# C-07_CPU_MISC.net
KiCad netlist of a schematic drawn in Altium Designer
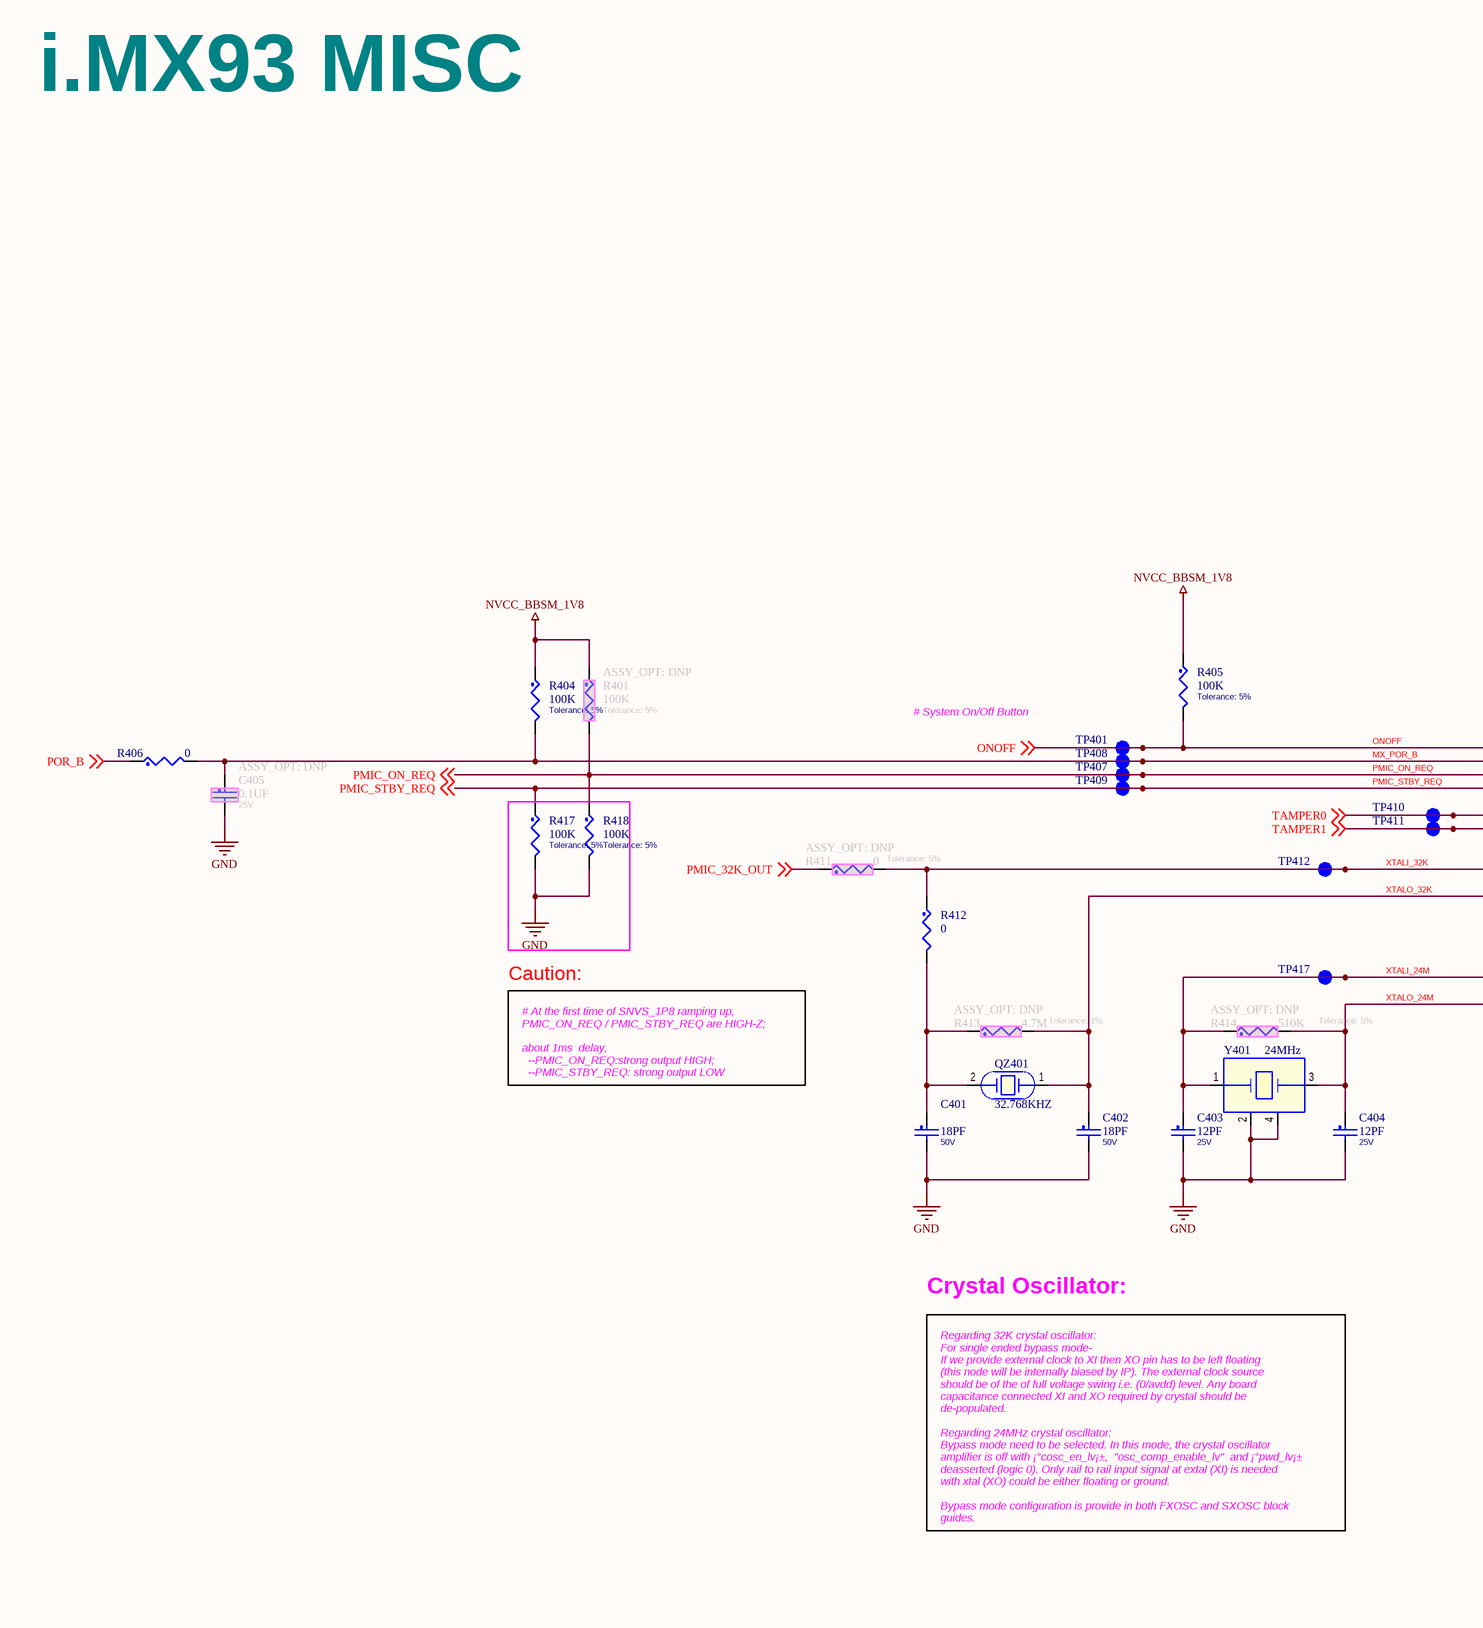
[diagram p0: C-07 CPU MISC.SchDoc, left]
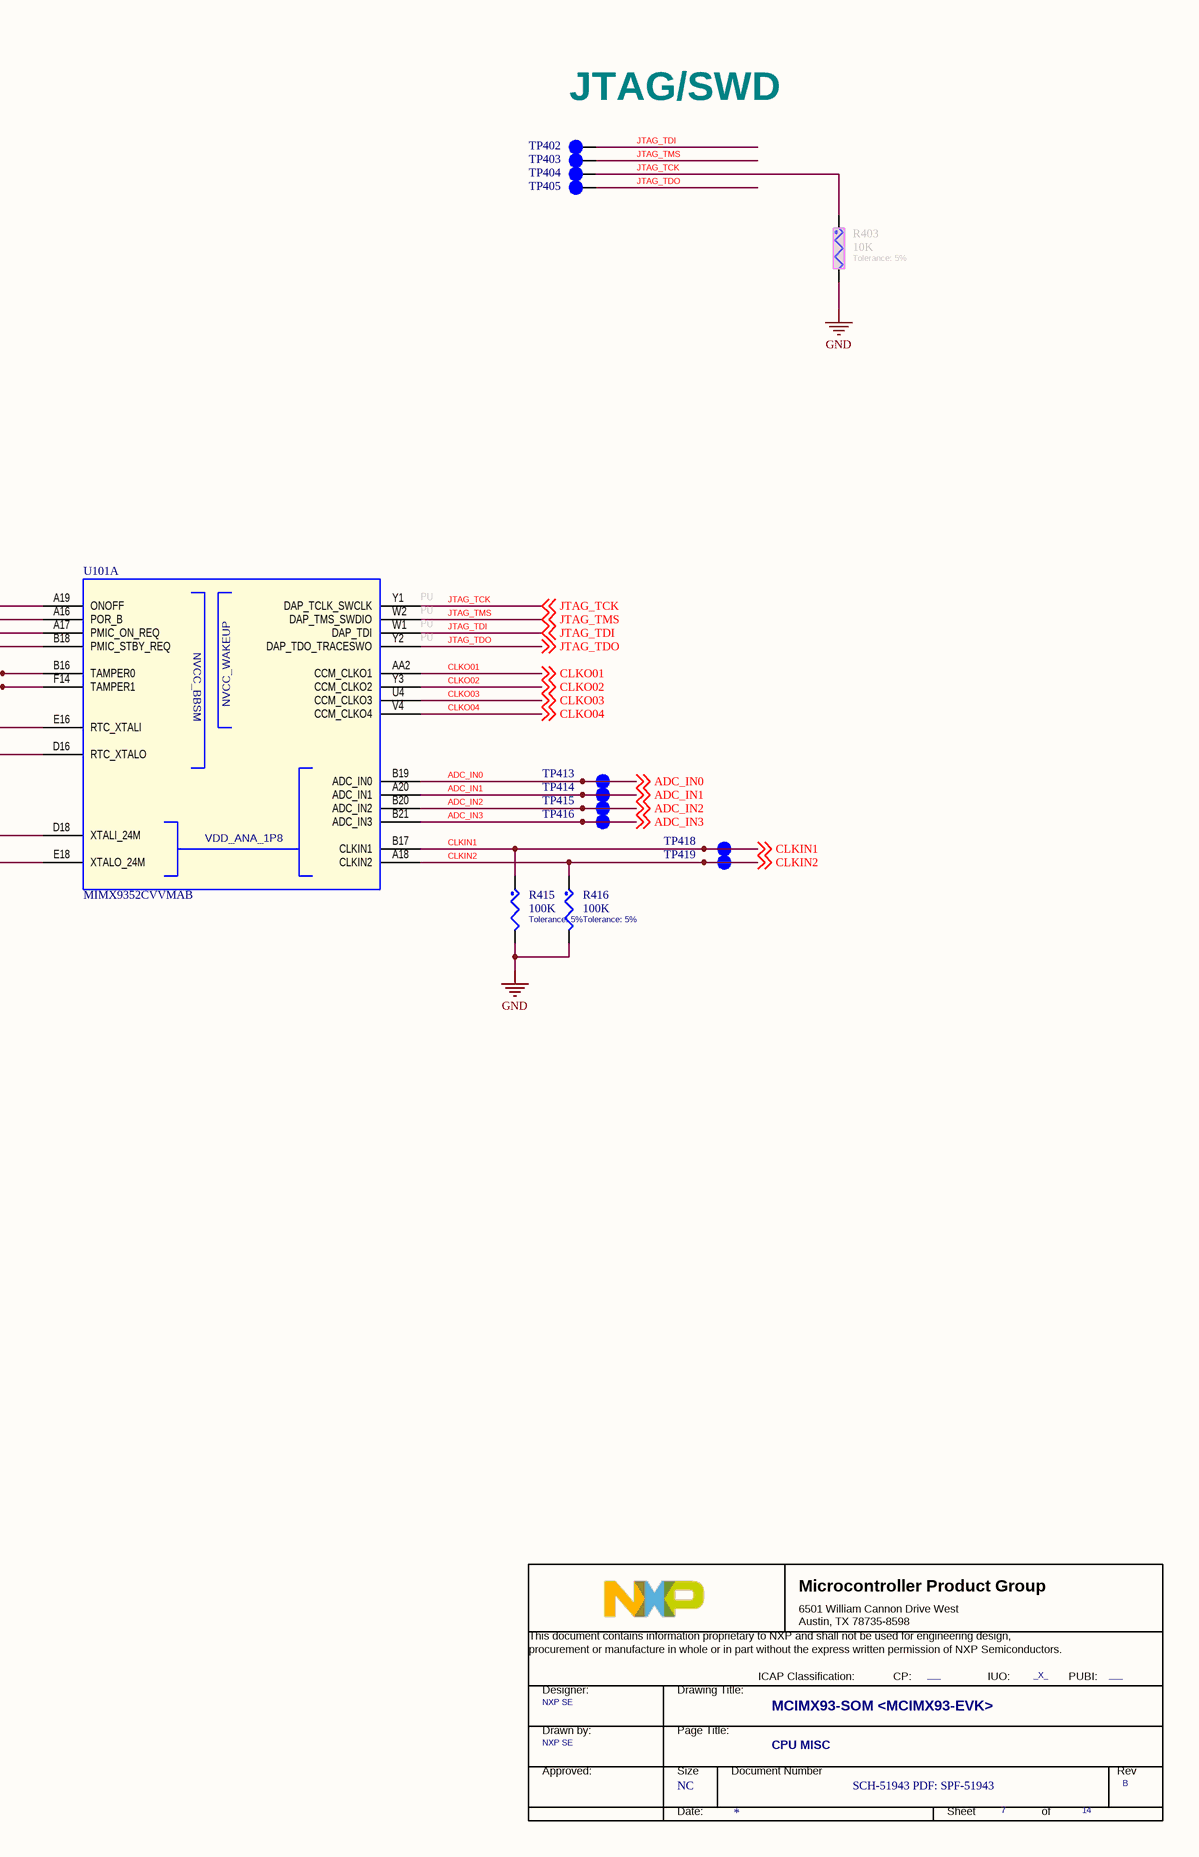
[diagram p1: C-07 CPU MISC.SchDoc, right]

(export (version "E")
  (design (tool "Eeschema 10.0.6"))
  (components
    (comp (ref "C401")
      (value "18PF")
      (footprint "0201_CC")
      (description "CAP CER 18pF 50V 5% C0G 0201")
      (fields (field (name "VOLTAGE") "50V") (field (name "TOLERANCE") "5%"))
      (libsource (lib "*") (part "CAP_NP"))
    )
    (comp (ref "C402")
      (value "18PF")
      (footprint "0201_CC")
      (description "CAP CER 18pF 50V 5% C0G 0201")
      (fields (field (name "TOLERANCE") "5%") (field (name "VOLTAGE") "50V"))
      (libsource (lib "*") (part "CAP_NP"))
    )
    (comp (ref "C403")
      (value "12PF")
      (footprint "0201_CC")
      (description "CAP CER 12PF 25V 5% C0G AEC-Q200 0201")
      (fields (field (name "TOLERANCE") "5%") (field (name "VOLTAGE") "25V"))
      (libsource (lib "*") (part "CAP_NP"))
    )
    (comp (ref "C404")
      (value "12PF")
      (footprint "0201_CC")
      (description "CAP CER 12PF 25V 5% C0G AEC-Q200 0201")
      (fields (field (name "TOLERANCE") "5%") (field (name "VOLTAGE") "25V"))
      (libsource (lib "*") (part "CAP_NP"))
    )
    (comp (ref "C405")
      (value "0.1UF")
      (footprint "0402_CC")
      (description "CAP CER 0.1UF 25V 10% X5R 0402")
      (fields (field (name "ASSY_OPT") "DNP") (field (name "VOLTAGE") "25V") (field (name "TOLERANCE") "10%"))
      (libsource (lib "*") (part "CAP_NP"))
    )
    (comp (ref "QZ401")
      (value "32.768KHZ")
      (footprint "XTAL2-3P2X1P5-SM")
      (description "XTAL 32.768KHZ 12.5PF 20PPM 3.2X1.5MM SMT")
      (libsource (lib "*") (part "XTAL"))
    )
    (comp (ref "R401")
      (value "100K")
      (footprint "0402_CC")
      (description "RES MF 100K 1/16W 5% 0402")
      (fields (field (name "ASSY_OPT") "DNP") (field (name "VOLTAGE") "50V") (field (name "TOLERANCE") "5%"))
      (libsource (lib "*") (part "RES"))
    )
    (comp (ref "R403")
      (value "10K")
      (footprint "0402_CC")
      (description "RES MF 10K 1/16W 5% 0402")
      (fields (field (name "TOLERANCE") "5%"))
      (libsource (lib "*") (part "RES"))
    )
    (comp (ref "R404")
      (value "100K")
      (footprint "0402_CC")
      (description "RES MF 100K 1/16W 5% 0402")
      (fields (field (name "TOLERANCE") "5%") (field (name "VOLTAGE") "50V"))
      (libsource (lib "*") (part "RES"))
    )
    (comp (ref "R405")
      (value "100K")
      (footprint "0402_CC")
      (description "RES MF 100K 1/16W 5% 0402")
      (fields (field (name "VOLTAGE") "50V") (field (name "TOLERANCE") "5%"))
      (libsource (lib "*") (part "RES"))
    )
    (comp (ref "R406")
      (value "0")
      (footprint "0201_CC")
      (description "RES MF ZERO OHM 1/20W -- 0201")
      (libsource (lib "*") (part "RES"))
    )
    (comp (ref "R411")
      (value "0")
      (footprint "0201_CC")
      (description "RES MF ZERO OHM 1/20W -- 0201")
      (fields (field (name "ASSY_OPT") "DNP") (field (name "TOLERANCE") "5%"))
      (libsource (lib "*") (part "RES"))
    )
    (comp (ref "R412")
      (value "0")
      (footprint "0201_CC")
      (description "RES MF ZERO OHM 1/20W -- 0201")
      (libsource (lib "*") (part "RES"))
    )
    (comp (ref "R413")
      (value "4.7M")
      (footprint "RC0402_25")
      (description "RES MF 4.7M  1/16W 1% 0402")
      (fields (field (name "ASSY_OPT") "DNP") (field (name "TOLERANCE") "1%") (field (name "VOLTAGE") "50V"))
      (libsource (lib "*") (part "RES"))
    )
    (comp (ref "R414")
      (value "510K")
      (footprint "0402_CC")
      (description "RES MF 510K 1/16W 5% 0402")
      (fields (field (name "ASSY_OPT") "DNP") (field (name "TOLERANCE") "5%"))
      (libsource (lib "*") (part "RES"))
    )
    (comp (ref "R415")
      (value "100K")
      (footprint "0402_CC")
      (description "RES MF 100K 1/16W 5% 0402")
      (fields (field (name "VOLTAGE") "50V") (field (name "TOLERANCE") "5%"))
      (libsource (lib "*") (part "RES"))
    )
    (comp (ref "R416")
      (value "100K")
      (footprint "0402_CC")
      (description "RES MF 100K 1/16W 5% 0402")
      (fields (field (name "VOLTAGE") "50V") (field (name "TOLERANCE") "5%"))
      (libsource (lib "*") (part "RES"))
    )
    (comp (ref "R417")
      (value "100K")
      (footprint "0402_CC")
      (description "RES MF 100K 1/16W 5% 0402")
      (fields (field (name "VOLTAGE") "50V") (field (name "TOLERANCE") "5%"))
      (libsource (lib "*") (part "RES"))
    )
    (comp (ref "R418")
      (value "100K")
      (footprint "0402_CC")
      (description "RES MF 100K 1/16W 5% 0402")
      (fields (field (name "VOLTAGE") "50V") (field (name "TOLERANCE") "5%"))
      (libsource (lib "*") (part "RES"))
    )
    (comp (ref "TP401")
      (value "tpad_020")
      (footprint "tpad_020")
      (description "TEST POINT PAD 0.5MM DIA SMT, NO PART TO ORDER")
      (libsource (lib "*") (part "TESTLOOP"))
    )
    (comp (ref "TP402")
      (value "tpad_020")
      (footprint "tpad_020")
      (description "TEST POINT PAD 0.5MM DIA SMT, NO PART TO ORDER")
      (libsource (lib "*") (part "TESTLOOP"))
    )
    (comp (ref "TP403")
      (value "tpad_020")
      (footprint "tpad_020")
      (description "TEST POINT PAD 0.5MM DIA SMT, NO PART TO ORDER")
      (libsource (lib "*") (part "TESTLOOP"))
    )
    (comp (ref "TP404")
      (value "tpad_020")
      (footprint "tpad_020")
      (description "TEST POINT PAD 0.5MM DIA SMT, NO PART TO ORDER")
      (libsource (lib "*") (part "TESTLOOP"))
    )
    (comp (ref "TP405")
      (value "tpad_020")
      (footprint "tpad_020")
      (description "TEST POINT PAD 0.5MM DIA SMT, NO PART TO ORDER")
      (libsource (lib "*") (part "TESTLOOP"))
    )
    (comp (ref "TP407")
      (value "tpad_020")
      (footprint "tpad_020")
      (description "TEST POINT PAD 0.5MM DIA SMT, NO PART TO ORDER")
      (libsource (lib "*") (part "TESTLOOP"))
    )
    (comp (ref "TP408")
      (value "tpad_020")
      (footprint "tpad_020")
      (description "TEST POINT PAD 0.5MM DIA SMT, NO PART TO ORDER")
      (libsource (lib "*") (part "TESTLOOP"))
    )
    (comp (ref "TP409")
      (value "tpad_020")
      (footprint "tpad_020")
      (description "TEST POINT PAD 0.5MM DIA SMT, NO PART TO ORDER")
      (libsource (lib "*") (part "TESTLOOP"))
    )
    (comp (ref "TP410")
      (value "tpad_020")
      (footprint "tpad_020")
      (description "TEST POINT PAD 0.5MM DIA SMT, NO PART TO ORDER")
      (libsource (lib "*") (part "TESTLOOP"))
    )
    (comp (ref "TP411")
      (value "tpad_020")
      (footprint "tpad_020")
      (description "TEST POINT PAD 0.5MM DIA SMT, NO PART TO ORDER")
      (libsource (lib "*") (part "TESTLOOP"))
    )
    (comp (ref "TP412")
      (value "TPAD_015")
      (footprint "TPAD_015")
      (description "TEST POINT PAD 15MIL DIA SMT, NO PART TO ORDER")
      (libsource (lib "*") (part "TESTLOOP"))
    )
    (comp (ref "TP413")
      (value "tpad_020")
      (footprint "tpad_020")
      (description "TEST POINT PAD 0.5MM DIA SMT, NO PART TO ORDER")
      (libsource (lib "*") (part "TESTLOOP"))
    )
    (comp (ref "TP414")
      (value "tpad_020")
      (footprint "tpad_020")
      (description "TEST POINT PAD 0.5MM DIA SMT, NO PART TO ORDER")
      (libsource (lib "*") (part "TESTLOOP"))
    )
    (comp (ref "TP415")
      (value "tpad_020")
      (footprint "tpad_020")
      (description "TEST POINT PAD 0.5MM DIA SMT, NO PART TO ORDER")
      (libsource (lib "*") (part "TESTLOOP"))
    )
    (comp (ref "TP416")
      (value "tpad_020")
      (footprint "tpad_020")
      (description "TEST POINT PAD 0.5MM DIA SMT, NO PART TO ORDER")
      (libsource (lib "*") (part "TESTLOOP"))
    )
    (comp (ref "TP417")
      (value "TPAD_015")
      (footprint "TPAD_015")
      (description "TEST POINT PAD 15MIL DIA SMT, NO PART TO ORDER")
      (libsource (lib "*") (part "TESTLOOP"))
    )
    (comp (ref "TP418")
      (value "tpad_020")
      (footprint "tpad_020")
      (description "TEST POINT PAD 0.5MM DIA SMT, NO PART TO ORDER")
      (libsource (lib "*") (part "TESTLOOP"))
    )
    (comp (ref "TP419")
      (value "tpad_020")
      (footprint "tpad_020")
      (description "TEST POINT PAD 0.5MM DIA SMT, NO PART TO ORDER")
      (libsource (lib "*") (part "TESTLOOP"))
    )
    (comp (ref "U101")
      (value "MIMX9352CVVMAB")
      (footprint "SKT_BGA306_0P5_SQ16P23_ELAST")
      (description "SUBASSEMBLY SKT 306 BGA ELASTOMER SMT 0.5MM 395H AU + IC CPU 1.7GHz -- FCBGA306")
      (libsource (lib "*") (part "MIMX9352DVNxLAA"))
    )
    (comp (ref "Y401")
      (value "24MHz")
      (footprint "xtlosc4_3p2x2p5mm_sm")
      (description "XTAL 24MHZ 9pF -- SMT 3.2X2.5MM")
      (libsource (lib "*") (part "XTAL_13"))
    )
  )
  (nets
    (net (code "1") (name "/MX_POR_B") (class "Default")
      (node (ref "C405") (pin "1") (pinfunction "1_1") (pintype "passive"))
      (node (ref "R404") (pin "2") (pinfunction "2_2") (pintype "passive"))
      (node (ref "R406") (pin "2") (pinfunction "2_2") (pintype "passive"))
      (node (ref "TP408") (pin "1") (pinfunction "Pin1_1") (pintype "passive"))
      (node (ref "U101") (pin "A16") (pinfunction "POR_B_A16") (pintype "passive"))
    )
    (net (code "2") (name "/XTALI_24M") (class "Default")
      (node (ref "C403") (pin "1") (pinfunction "1_1") (pintype "passive"))
      (node (ref "R414") (pin "1") (pinfunction "1_1") (pintype "passive"))
      (node (ref "TP417") (pin "1") (pinfunction "Pin1_1") (pintype "passive"))
      (node (ref "U101") (pin "D18") (pinfunction "XTALI_24M_D18") (pintype "passive"))
      (node (ref "Y401") (pin "1") (pinfunction "1_1") (pintype "passive"))
    )
    (net (code "3") (name "/XTALI_32K") (class "Default")
      (node (ref "R411") (pin "2") (pinfunction "2_2") (pintype "passive"))
      (node (ref "R412") (pin "1") (pinfunction "1_1") (pintype "passive"))
      (node (ref "TP412") (pin "1") (pinfunction "Pin1_1") (pintype "passive"))
      (node (ref "U101") (pin "E16") (pinfunction "RTC_XTALI_E16") (pintype "passive"))
    )
    (net (code "4") (name "/XTALO_24M") (class "Default")
      (node (ref "C404") (pin "1") (pinfunction "1_1") (pintype "passive"))
      (node (ref "R414") (pin "2") (pinfunction "2_2") (pintype "passive"))
      (node (ref "U101") (pin "E18") (pinfunction "XTALO_24M_E18") (pintype "passive"))
      (node (ref "Y401") (pin "3") (pinfunction "3_3") (pintype "passive"))
    )
    (net (code "5") (name "/XTALO_32K") (class "Default")
      (node (ref "C402") (pin "1") (pinfunction "1_1") (pintype "passive"))
      (node (ref "QZ401") (pin "1") (pinfunction "1_1") (pintype "passive"))
      (node (ref "R413") (pin "2") (pinfunction "2_2") (pintype "passive"))
      (node (ref "U101") (pin "D16") (pinfunction "RTC_XTALO_D16") (pintype "passive"))
    )
    (net (code "6") (name "ADC_IN0") (class "Default")
      (node (ref "TP413") (pin "1") (pinfunction "Pin1_1") (pintype "passive"))
      (node (ref "U101") (pin "B19") (pinfunction "ADC_IN0_B19") (pintype "passive"))
    )
    (net (code "7") (name "ADC_IN1") (class "Default")
      (node (ref "TP414") (pin "1") (pinfunction "Pin1_1") (pintype "passive"))
      (node (ref "U101") (pin "A20") (pinfunction "ADC_IN1_A20") (pintype "passive"))
    )
    (net (code "8") (name "ADC_IN2") (class "Default")
      (node (ref "TP415") (pin "1") (pinfunction "Pin1_1") (pintype "passive"))
      (node (ref "U101") (pin "B20") (pinfunction "ADC_IN2_B20") (pintype "passive"))
    )
    (net (code "9") (name "ADC_IN3") (class "Default")
      (node (ref "TP416") (pin "1") (pinfunction "Pin1_1") (pintype "passive"))
      (node (ref "U101") (pin "B21") (pinfunction "ADC_IN3_B21") (pintype "passive"))
    )
    (net (code "10") (name "CLKIN1") (class "Default")
      (node (ref "R415") (pin "1") (pinfunction "1_1") (pintype "passive"))
      (node (ref "TP418") (pin "1") (pinfunction "Pin1_1") (pintype "passive"))
      (node (ref "U101") (pin "B17") (pinfunction "CLKIN1_B17") (pintype "passive"))
    )
    (net (code "11") (name "CLKIN2") (class "Default")
      (node (ref "R416") (pin "1") (pinfunction "1_1") (pintype "passive"))
      (node (ref "TP419") (pin "1") (pinfunction "Pin1_1") (pintype "passive"))
      (node (ref "U101") (pin "A18") (pinfunction "CLKIN2_A18") (pintype "passive"))
    )
    (net (code "12") (name "CLKO01") (class "Default")
      (node (ref "U101") (pin "AA2") (pinfunction "CCM_CLKO1_AA2") (pintype "passive"))
    )
    (net (code "13") (name "CLKO02") (class "Default")
      (node (ref "U101") (pin "Y3") (pinfunction "CCM_CLKO2_Y3") (pintype "passive"))
    )
    (net (code "14") (name "CLKO03") (class "Default")
      (node (ref "U101") (pin "U4") (pinfunction "CCM_CLKO3_U4") (pintype "passive"))
    )
    (net (code "15") (name "CLKO04") (class "Default")
      (node (ref "U101") (pin "V4") (pinfunction "CCM_CLKO4_V4") (pintype "passive"))
    )
    (net (code "16") (name "GND") (class "Default")
      (node (ref "C401") (pin "2") (pinfunction "2_2") (pintype "passive"))
      (node (ref "C402") (pin "2") (pinfunction "2_2") (pintype "passive"))
      (node (ref "C403") (pin "2") (pinfunction "2_2") (pintype "passive"))
      (node (ref "C404") (pin "2") (pinfunction "2_2") (pintype "passive"))
      (node (ref "C405") (pin "2") (pinfunction "2_2") (pintype "passive"))
      (node (ref "R403") (pin "2") (pinfunction "2_2") (pintype "passive"))
      (node (ref "R415") (pin "2") (pinfunction "2_2") (pintype "passive"))
      (node (ref "R416") (pin "2") (pinfunction "2_2") (pintype "passive"))
      (node (ref "R417") (pin "2") (pinfunction "2_2") (pintype "passive"))
      (node (ref "R418") (pin "2") (pinfunction "2_2") (pintype "passive"))
      (node (ref "Y401") (pin "2") (pinfunction "2_2") (pintype "passive"))
      (node (ref "Y401") (pin "4") (pinfunction "4_4") (pintype "passive"))
    )
    (net (code "17") (name "JTAG_TCK") (class "Default")
      (node (ref "R403") (pin "1") (pinfunction "1_1") (pintype "passive"))
      (node (ref "TP404") (pin "1") (pinfunction "Pin1_1") (pintype "passive"))
      (node (ref "U101") (pin "Y1") (pinfunction "DAP_TCLK_SWCLK_Y1") (pintype "passive"))
    )
    (net (code "18") (name "JTAG_TDI") (class "Default")
      (node (ref "TP402") (pin "1") (pinfunction "Pin1_1") (pintype "passive"))
      (node (ref "U101") (pin "W1") (pinfunction "DAP_TDI_W1") (pintype "passive"))
    )
    (net (code "19") (name "JTAG_TDO") (class "Default")
      (node (ref "TP405") (pin "1") (pinfunction "Pin1_1") (pintype "passive"))
      (node (ref "U101") (pin "Y2") (pinfunction "DAP_TDO_TRACESWO_Y2") (pintype "passive"))
    )
    (net (code "20") (name "JTAG_TMS") (class "Default")
      (node (ref "TP403") (pin "1") (pinfunction "Pin1_1") (pintype "passive"))
      (node (ref "U101") (pin "W2") (pinfunction "DAP_TMS_SWDIO_W2") (pintype "passive"))
    )
    (net (code "21") (name "NVCC_BBSM_1V8") (class "Default")
      (node (ref "R401") (pin "1") (pinfunction "1_1") (pintype "passive"))
      (node (ref "R404") (pin "1") (pinfunction "1_1") (pintype "passive"))
      (node (ref "R405") (pin "1") (pinfunction "1_1") (pintype "passive"))
    )
    (net (code "22") (name "Net-(C401-Pad1)") (class "Default")
      (node (ref "C401") (pin "1") (pinfunction "1_1") (pintype "passive"))
      (node (ref "QZ401") (pin "2") (pinfunction "2_2") (pintype "passive"))
      (node (ref "R412") (pin "2") (pinfunction "2_2") (pintype "passive"))
      (node (ref "R413") (pin "1") (pinfunction "1_1") (pintype "passive"))
    )
    (net (code "23") (name "ONOFF") (class "Default")
      (node (ref "R405") (pin "2") (pinfunction "2_2") (pintype "passive"))
      (node (ref "TP401") (pin "1") (pinfunction "Pin1_1") (pintype "passive"))
      (node (ref "U101") (pin "A19") (pinfunction "ONOFF_A19") (pintype "passive"))
    )
    (net (code "24") (name "PMIC_32K_OUT") (class "Default")
      (node (ref "R411") (pin "1") (pinfunction "1_1") (pintype "passive"))
    )
    (net (code "25") (name "PMIC_ON_REQ") (class "Default")
      (node (ref "R401") (pin "2") (pinfunction "2_2") (pintype "passive"))
      (node (ref "R418") (pin "1") (pinfunction "1_1") (pintype "passive"))
      (node (ref "TP407") (pin "1") (pinfunction "Pin1_1") (pintype "passive"))
      (node (ref "U101") (pin "A17") (pinfunction "PMIC_ON_REQ_A17") (pintype "passive"))
    )
    (net (code "26") (name "PMIC_STBY_REQ") (class "Default")
      (node (ref "R417") (pin "1") (pinfunction "1_1") (pintype "passive"))
      (node (ref "TP409") (pin "1") (pinfunction "Pin1_1") (pintype "passive"))
      (node (ref "U101") (pin "B18") (pinfunction "PMIC_STBY_REQ_B18") (pintype "passive"))
    )
    (net (code "27") (name "POR_B") (class "Default")
      (node (ref "R406") (pin "1") (pinfunction "1_1") (pintype "passive"))
    )
    (net (code "28") (name "TAMPER0") (class "Default")
      (node (ref "TP410") (pin "1") (pinfunction "Pin1_1") (pintype "passive"))
      (node (ref "U101") (pin "B16") (pinfunction "TAMPER0_B16") (pintype "passive"))
    )
    (net (code "29") (name "TAMPER1") (class "Default")
      (node (ref "TP411") (pin "1") (pinfunction "Pin1_1") (pintype "passive"))
      (node (ref "U101") (pin "F14") (pinfunction "TAMPER1_F14") (pintype "passive"))
    )
  )
)
